# 09-Connectors.net
KiCad netlist of a schematic drawn in Altium Designer
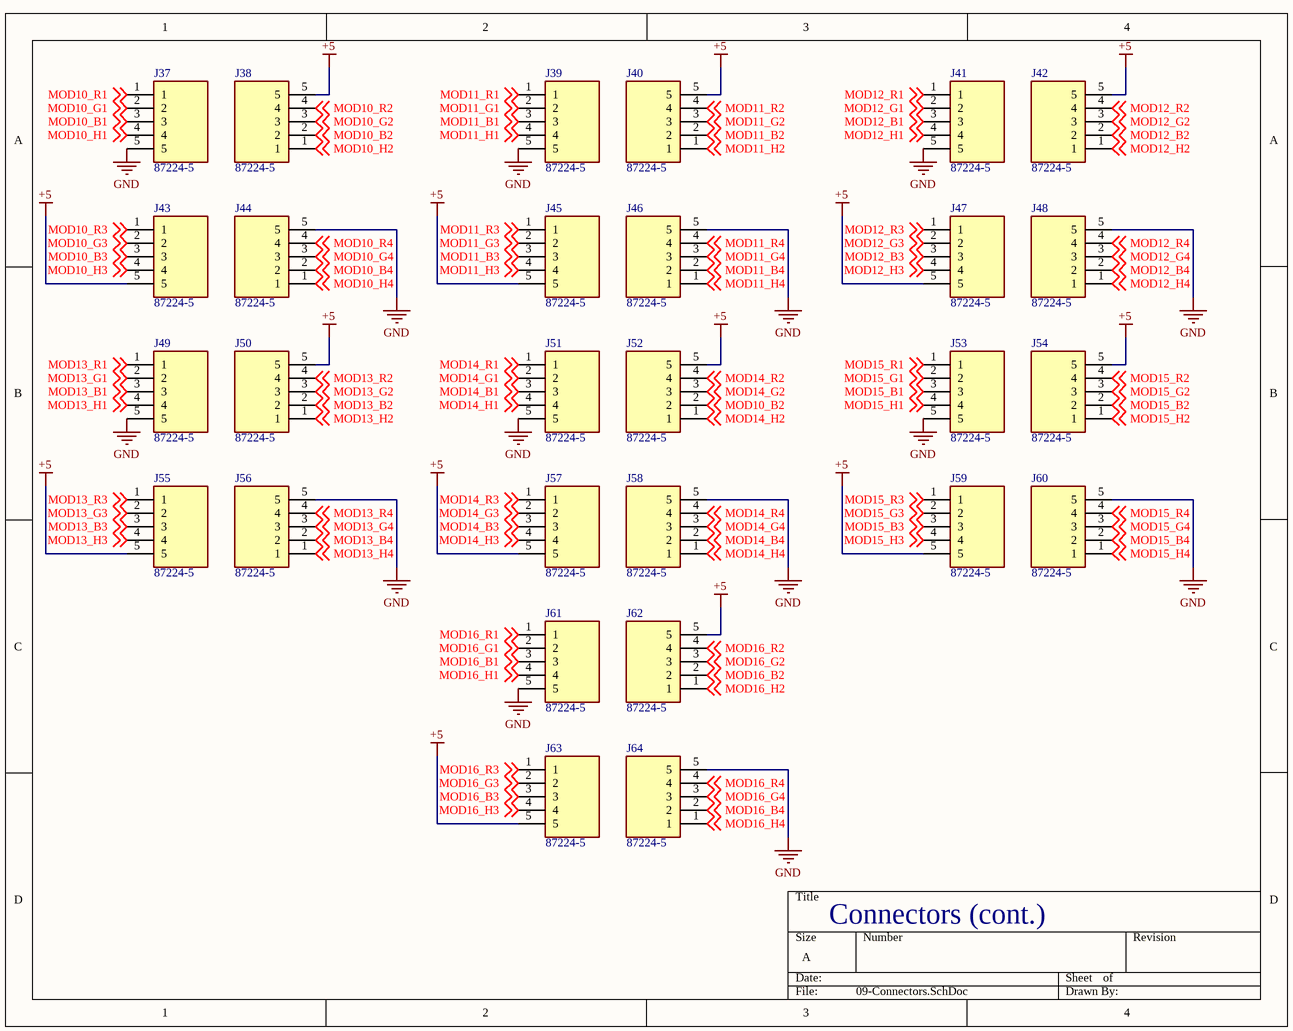
[diagram p0: 09-Connectors.SchDoc]

(export (version "E")
  (design (tool "Eeschema 10.0.6"))
  (components
    (comp (ref "J37")
      (value "87224-5")
      (footprint "TE_87224-5")
      (description "Conn Unshrouded Header HDR 5 POS 2.54mm Solder ST Thru-Hole")
      (fields (field (name "MF") "TE Connectivity"))
      (libsource (lib "chess_module") (part "87224-5"))
    )
    (comp (ref "J38")
      (value "87224-5")
      (footprint "TE_87224-5")
      (description "Conn Unshrouded Header HDR 5 POS 2.54mm Solder ST Thru-Hole")
      (fields (field (name "MF") "TE Connectivity"))
      (libsource (lib "") (part "87224-5_1"))
    )
    (comp (ref "J39")
      (value "87224-5")
      (footprint "TE_87224-5")
      (description "Conn Unshrouded Header HDR 5 POS 2.54mm Solder ST Thru-Hole")
      (fields (field (name "MF") "TE Connectivity"))
      (libsource (lib "chess_module") (part "87224-5"))
    )
    (comp (ref "J40")
      (value "87224-5")
      (footprint "TE_87224-5")
      (description "Conn Unshrouded Header HDR 5 POS 2.54mm Solder ST Thru-Hole")
      (fields (field (name "MF") "TE Connectivity"))
      (libsource (lib "") (part "87224-5_1"))
    )
    (comp (ref "J41")
      (value "87224-5")
      (footprint "TE_87224-5")
      (description "Conn Unshrouded Header HDR 5 POS 2.54mm Solder ST Thru-Hole")
      (fields (field (name "MF") "TE Connectivity"))
      (libsource (lib "chess_module") (part "87224-5"))
    )
    (comp (ref "J42")
      (value "87224-5")
      (footprint "TE_87224-5")
      (description "Conn Unshrouded Header HDR 5 POS 2.54mm Solder ST Thru-Hole")
      (fields (field (name "MF") "TE Connectivity"))
      (libsource (lib "") (part "87224-5_1"))
    )
    (comp (ref "J43")
      (value "87224-5")
      (footprint "TE_87224-5")
      (description "Conn Unshrouded Header HDR 5 POS 2.54mm Solder ST Thru-Hole")
      (fields (field (name "MF") "TE Connectivity"))
      (libsource (lib "chess_module") (part "87224-5"))
    )
    (comp (ref "J44")
      (value "87224-5")
      (footprint "TE_87224-5")
      (description "Conn Unshrouded Header HDR 5 POS 2.54mm Solder ST Thru-Hole")
      (fields (field (name "MF") "TE Connectivity"))
      (libsource (lib "") (part "87224-5_1"))
    )
    (comp (ref "J45")
      (value "87224-5")
      (footprint "TE_87224-5")
      (description "Conn Unshrouded Header HDR 5 POS 2.54mm Solder ST Thru-Hole")
      (fields (field (name "MF") "TE Connectivity"))
      (libsource (lib "chess_module") (part "87224-5"))
    )
    (comp (ref "J46")
      (value "87224-5")
      (footprint "TE_87224-5")
      (description "Conn Unshrouded Header HDR 5 POS 2.54mm Solder ST Thru-Hole")
      (fields (field (name "MF") "TE Connectivity"))
      (libsource (lib "") (part "87224-5_1"))
    )
    (comp (ref "J47")
      (value "87224-5")
      (footprint "TE_87224-5")
      (description "Conn Unshrouded Header HDR 5 POS 2.54mm Solder ST Thru-Hole")
      (fields (field (name "MF") "TE Connectivity"))
      (libsource (lib "chess_module") (part "87224-5"))
    )
    (comp (ref "J48")
      (value "87224-5")
      (footprint "TE_87224-5")
      (description "Conn Unshrouded Header HDR 5 POS 2.54mm Solder ST Thru-Hole")
      (fields (field (name "MF") "TE Connectivity"))
      (libsource (lib "") (part "87224-5_1"))
    )
    (comp (ref "J49")
      (value "87224-5")
      (footprint "TE_87224-5")
      (description "Conn Unshrouded Header HDR 5 POS 2.54mm Solder ST Thru-Hole")
      (fields (field (name "MF") "TE Connectivity"))
      (libsource (lib "chess_module") (part "87224-5"))
    )
    (comp (ref "J50")
      (value "87224-5")
      (footprint "TE_87224-5")
      (description "Conn Unshrouded Header HDR 5 POS 2.54mm Solder ST Thru-Hole")
      (fields (field (name "MF") "TE Connectivity"))
      (libsource (lib "") (part "87224-5_1"))
    )
    (comp (ref "J51")
      (value "87224-5")
      (footprint "TE_87224-5")
      (description "Conn Unshrouded Header HDR 5 POS 2.54mm Solder ST Thru-Hole")
      (fields (field (name "MF") "TE Connectivity"))
      (libsource (lib "chess_module") (part "87224-5"))
    )
    (comp (ref "J52")
      (value "87224-5")
      (footprint "TE_87224-5")
      (description "Conn Unshrouded Header HDR 5 POS 2.54mm Solder ST Thru-Hole")
      (fields (field (name "MF") "TE Connectivity"))
      (libsource (lib "") (part "87224-5_1"))
    )
    (comp (ref "J53")
      (value "87224-5")
      (footprint "TE_87224-5")
      (description "Conn Unshrouded Header HDR 5 POS 2.54mm Solder ST Thru-Hole")
      (fields (field (name "MF") "TE Connectivity"))
      (libsource (lib "chess_module") (part "87224-5"))
    )
    (comp (ref "J54")
      (value "87224-5")
      (footprint "TE_87224-5")
      (description "Conn Unshrouded Header HDR 5 POS 2.54mm Solder ST Thru-Hole")
      (fields (field (name "MF") "TE Connectivity"))
      (libsource (lib "") (part "87224-5_1"))
    )
    (comp (ref "J55")
      (value "87224-5")
      (footprint "TE_87224-5")
      (description "Conn Unshrouded Header HDR 5 POS 2.54mm Solder ST Thru-Hole")
      (fields (field (name "MF") "TE Connectivity"))
      (libsource (lib "chess_module") (part "87224-5"))
    )
    (comp (ref "J56")
      (value "87224-5")
      (footprint "TE_87224-5")
      (description "Conn Unshrouded Header HDR 5 POS 2.54mm Solder ST Thru-Hole")
      (fields (field (name "MF") "TE Connectivity"))
      (libsource (lib "") (part "87224-5_1"))
    )
    (comp (ref "J57")
      (value "87224-5")
      (footprint "TE_87224-5")
      (description "Conn Unshrouded Header HDR 5 POS 2.54mm Solder ST Thru-Hole")
      (fields (field (name "MF") "TE Connectivity"))
      (libsource (lib "chess_module") (part "87224-5"))
    )
    (comp (ref "J58")
      (value "87224-5")
      (footprint "TE_87224-5")
      (description "Conn Unshrouded Header HDR 5 POS 2.54mm Solder ST Thru-Hole")
      (fields (field (name "MF") "TE Connectivity"))
      (libsource (lib "") (part "87224-5_1"))
    )
    (comp (ref "J59")
      (value "87224-5")
      (footprint "TE_87224-5")
      (description "Conn Unshrouded Header HDR 5 POS 2.54mm Solder ST Thru-Hole")
      (fields (field (name "MF") "TE Connectivity"))
      (libsource (lib "chess_module") (part "87224-5"))
    )
    (comp (ref "J60")
      (value "87224-5")
      (footprint "TE_87224-5")
      (description "Conn Unshrouded Header HDR 5 POS 2.54mm Solder ST Thru-Hole")
      (fields (field (name "MF") "TE Connectivity"))
      (libsource (lib "") (part "87224-5_1"))
    )
    (comp (ref "J61")
      (value "87224-5")
      (footprint "TE_87224-5")
      (description "Conn Unshrouded Header HDR 5 POS 2.54mm Solder ST Thru-Hole")
      (fields (field (name "MF") "TE Connectivity"))
      (libsource (lib "chess_module") (part "87224-5"))
    )
    (comp (ref "J62")
      (value "87224-5")
      (footprint "TE_87224-5")
      (description "Conn Unshrouded Header HDR 5 POS 2.54mm Solder ST Thru-Hole")
      (fields (field (name "MF") "TE Connectivity"))
      (libsource (lib "") (part "87224-5_1"))
    )
    (comp (ref "J63")
      (value "87224-5")
      (footprint "TE_87224-5")
      (description "Conn Unshrouded Header HDR 5 POS 2.54mm Solder ST Thru-Hole")
      (fields (field (name "MF") "TE Connectivity"))
      (libsource (lib "chess_module") (part "87224-5"))
    )
    (comp (ref "J64")
      (value "87224-5")
      (footprint "TE_87224-5")
      (description "Conn Unshrouded Header HDR 5 POS 2.54mm Solder ST Thru-Hole")
      (fields (field (name "MF") "TE Connectivity"))
      (libsource (lib "") (part "87224-5_1"))
    )
  )
  (nets
    (net (code "1") (name "+5") (class "Default")
      (node (ref "J38") (pin "5") (pinfunction "5_5") (pintype "passive"))
      (node (ref "J40") (pin "5") (pinfunction "5_5") (pintype "passive"))
      (node (ref "J42") (pin "5") (pinfunction "5_5") (pintype "passive"))
      (node (ref "J43") (pin "5") (pinfunction "5_5") (pintype "passive"))
      (node (ref "J45") (pin "5") (pinfunction "5_5") (pintype "passive"))
      (node (ref "J47") (pin "5") (pinfunction "5_5") (pintype "passive"))
      (node (ref "J50") (pin "5") (pinfunction "5_5") (pintype "passive"))
      (node (ref "J52") (pin "5") (pinfunction "5_5") (pintype "passive"))
      (node (ref "J54") (pin "5") (pinfunction "5_5") (pintype "passive"))
      (node (ref "J55") (pin "5") (pinfunction "5_5") (pintype "passive"))
      (node (ref "J57") (pin "5") (pinfunction "5_5") (pintype "passive"))
      (node (ref "J59") (pin "5") (pinfunction "5_5") (pintype "passive"))
      (node (ref "J62") (pin "5") (pinfunction "5_5") (pintype "passive"))
      (node (ref "J63") (pin "5") (pinfunction "5_5") (pintype "passive"))
    )
    (net (code "2") (name "GND") (class "Default")
      (node (ref "J37") (pin "5") (pinfunction "5_5") (pintype "passive"))
      (node (ref "J39") (pin "5") (pinfunction "5_5") (pintype "passive"))
      (node (ref "J41") (pin "5") (pinfunction "5_5") (pintype "passive"))
      (node (ref "J44") (pin "5") (pinfunction "5_5") (pintype "passive"))
      (node (ref "J46") (pin "5") (pinfunction "5_5") (pintype "passive"))
      (node (ref "J48") (pin "5") (pinfunction "5_5") (pintype "passive"))
      (node (ref "J49") (pin "5") (pinfunction "5_5") (pintype "passive"))
      (node (ref "J51") (pin "5") (pinfunction "5_5") (pintype "passive"))
      (node (ref "J53") (pin "5") (pinfunction "5_5") (pintype "passive"))
      (node (ref "J56") (pin "5") (pinfunction "5_5") (pintype "passive"))
      (node (ref "J58") (pin "5") (pinfunction "5_5") (pintype "passive"))
      (node (ref "J60") (pin "5") (pinfunction "5_5") (pintype "passive"))
      (node (ref "J61") (pin "5") (pinfunction "5_5") (pintype "passive"))
      (node (ref "J64") (pin "5") (pinfunction "5_5") (pintype "passive"))
    )
    (net (code "3") (name "MOD10_B1") (class "Default")
      (node (ref "J37") (pin "3") (pinfunction "3_3") (pintype "passive"))
    )
    (net (code "4") (name "MOD10_B2") (class "Default")
      (node (ref "J38") (pin "2") (pinfunction "2_2") (pintype "passive"))
      (node (ref "J52") (pin "2") (pinfunction "2_2") (pintype "passive"))
    )
    (net (code "5") (name "MOD10_B3") (class "Default")
      (node (ref "J43") (pin "3") (pinfunction "3_3") (pintype "passive"))
    )
    (net (code "6") (name "MOD10_B4") (class "Default")
      (node (ref "J44") (pin "2") (pinfunction "2_2") (pintype "passive"))
    )
    (net (code "7") (name "MOD10_G1") (class "Default")
      (node (ref "J37") (pin "2") (pinfunction "2_2") (pintype "passive"))
    )
    (net (code "8") (name "MOD10_G2") (class "Default")
      (node (ref "J38") (pin "3") (pinfunction "3_3") (pintype "passive"))
    )
    (net (code "9") (name "MOD10_G3") (class "Default")
      (node (ref "J43") (pin "2") (pinfunction "2_2") (pintype "passive"))
    )
    (net (code "10") (name "MOD10_G4") (class "Default")
      (node (ref "J44") (pin "3") (pinfunction "3_3") (pintype "passive"))
    )
    (net (code "11") (name "MOD10_H1") (class "Default")
      (node (ref "J37") (pin "4") (pinfunction "4_4") (pintype "passive"))
    )
    (net (code "12") (name "MOD10_H2") (class "Default")
      (node (ref "J38") (pin "1") (pinfunction "1_1") (pintype "passive"))
    )
    (net (code "13") (name "MOD10_H3") (class "Default")
      (node (ref "J43") (pin "4") (pinfunction "4_4") (pintype "passive"))
    )
    (net (code "14") (name "MOD10_H4") (class "Default")
      (node (ref "J44") (pin "1") (pinfunction "1_1") (pintype "passive"))
    )
    (net (code "15") (name "MOD10_R1") (class "Default")
      (node (ref "J37") (pin "1") (pinfunction "1_1") (pintype "passive"))
    )
    (net (code "16") (name "MOD10_R2") (class "Default")
      (node (ref "J38") (pin "4") (pinfunction "4_4") (pintype "passive"))
    )
    (net (code "17") (name "MOD10_R3") (class "Default")
      (node (ref "J43") (pin "1") (pinfunction "1_1") (pintype "passive"))
    )
    (net (code "18") (name "MOD10_R4") (class "Default")
      (node (ref "J44") (pin "4") (pinfunction "4_4") (pintype "passive"))
    )
    (net (code "19") (name "MOD11_B1") (class "Default")
      (node (ref "J39") (pin "3") (pinfunction "3_3") (pintype "passive"))
    )
    (net (code "20") (name "MOD11_B2") (class "Default")
      (node (ref "J40") (pin "2") (pinfunction "2_2") (pintype "passive"))
    )
    (net (code "21") (name "MOD11_B3") (class "Default")
      (node (ref "J45") (pin "3") (pinfunction "3_3") (pintype "passive"))
    )
    (net (code "22") (name "MOD11_B4") (class "Default")
      (node (ref "J46") (pin "2") (pinfunction "2_2") (pintype "passive"))
    )
    (net (code "23") (name "MOD11_G1") (class "Default")
      (node (ref "J39") (pin "2") (pinfunction "2_2") (pintype "passive"))
    )
    (net (code "24") (name "MOD11_G2") (class "Default")
      (node (ref "J40") (pin "3") (pinfunction "3_3") (pintype "passive"))
    )
    (net (code "25") (name "MOD11_G3") (class "Default")
      (node (ref "J45") (pin "2") (pinfunction "2_2") (pintype "passive"))
    )
    (net (code "26") (name "MOD11_G4") (class "Default")
      (node (ref "J46") (pin "3") (pinfunction "3_3") (pintype "passive"))
    )
    (net (code "27") (name "MOD11_H1") (class "Default")
      (node (ref "J39") (pin "4") (pinfunction "4_4") (pintype "passive"))
    )
    (net (code "28") (name "MOD11_H2") (class "Default")
      (node (ref "J40") (pin "1") (pinfunction "1_1") (pintype "passive"))
    )
    (net (code "29") (name "MOD11_H3") (class "Default")
      (node (ref "J45") (pin "4") (pinfunction "4_4") (pintype "passive"))
    )
    (net (code "30") (name "MOD11_H4") (class "Default")
      (node (ref "J46") (pin "1") (pinfunction "1_1") (pintype "passive"))
    )
    (net (code "31") (name "MOD11_R1") (class "Default")
      (node (ref "J39") (pin "1") (pinfunction "1_1") (pintype "passive"))
    )
    (net (code "32") (name "MOD11_R2") (class "Default")
      (node (ref "J40") (pin "4") (pinfunction "4_4") (pintype "passive"))
    )
    (net (code "33") (name "MOD11_R3") (class "Default")
      (node (ref "J45") (pin "1") (pinfunction "1_1") (pintype "passive"))
    )
    (net (code "34") (name "MOD11_R4") (class "Default")
      (node (ref "J46") (pin "4") (pinfunction "4_4") (pintype "passive"))
    )
    (net (code "35") (name "MOD12_B1") (class "Default")
      (node (ref "J41") (pin "3") (pinfunction "3_3") (pintype "passive"))
    )
    (net (code "36") (name "MOD12_B2") (class "Default")
      (node (ref "J42") (pin "2") (pinfunction "2_2") (pintype "passive"))
    )
    (net (code "37") (name "MOD12_B3") (class "Default")
      (node (ref "J47") (pin "3") (pinfunction "3_3") (pintype "passive"))
    )
    (net (code "38") (name "MOD12_B4") (class "Default")
      (node (ref "J48") (pin "2") (pinfunction "2_2") (pintype "passive"))
    )
    (net (code "39") (name "MOD12_G1") (class "Default")
      (node (ref "J41") (pin "2") (pinfunction "2_2") (pintype "passive"))
    )
    (net (code "40") (name "MOD12_G2") (class "Default")
      (node (ref "J42") (pin "3") (pinfunction "3_3") (pintype "passive"))
    )
    (net (code "41") (name "MOD12_G3") (class "Default")
      (node (ref "J47") (pin "2") (pinfunction "2_2") (pintype "passive"))
    )
    (net (code "42") (name "MOD12_G4") (class "Default")
      (node (ref "J48") (pin "3") (pinfunction "3_3") (pintype "passive"))
    )
    (net (code "43") (name "MOD12_H1") (class "Default")
      (node (ref "J41") (pin "4") (pinfunction "4_4") (pintype "passive"))
    )
    (net (code "44") (name "MOD12_H2") (class "Default")
      (node (ref "J42") (pin "1") (pinfunction "1_1") (pintype "passive"))
    )
    (net (code "45") (name "MOD12_H3") (class "Default")
      (node (ref "J47") (pin "4") (pinfunction "4_4") (pintype "passive"))
    )
    (net (code "46") (name "MOD12_H4") (class "Default")
      (node (ref "J48") (pin "1") (pinfunction "1_1") (pintype "passive"))
    )
    (net (code "47") (name "MOD12_R1") (class "Default")
      (node (ref "J41") (pin "1") (pinfunction "1_1") (pintype "passive"))
    )
    (net (code "48") (name "MOD12_R2") (class "Default")
      (node (ref "J42") (pin "4") (pinfunction "4_4") (pintype "passive"))
    )
    (net (code "49") (name "MOD12_R3") (class "Default")
      (node (ref "J47") (pin "1") (pinfunction "1_1") (pintype "passive"))
    )
    (net (code "50") (name "MOD12_R4") (class "Default")
      (node (ref "J48") (pin "4") (pinfunction "4_4") (pintype "passive"))
    )
    (net (code "51") (name "MOD13_B1") (class "Default")
      (node (ref "J49") (pin "3") (pinfunction "3_3") (pintype "passive"))
    )
    (net (code "52") (name "MOD13_B2") (class "Default")
      (node (ref "J50") (pin "2") (pinfunction "2_2") (pintype "passive"))
    )
    (net (code "53") (name "MOD13_B3") (class "Default")
      (node (ref "J55") (pin "3") (pinfunction "3_3") (pintype "passive"))
    )
    (net (code "54") (name "MOD13_B4") (class "Default")
      (node (ref "J56") (pin "2") (pinfunction "2_2") (pintype "passive"))
    )
    (net (code "55") (name "MOD13_G1") (class "Default")
      (node (ref "J49") (pin "2") (pinfunction "2_2") (pintype "passive"))
    )
    (net (code "56") (name "MOD13_G2") (class "Default")
      (node (ref "J50") (pin "3") (pinfunction "3_3") (pintype "passive"))
    )
    (net (code "57") (name "MOD13_G3") (class "Default")
      (node (ref "J55") (pin "2") (pinfunction "2_2") (pintype "passive"))
    )
    (net (code "58") (name "MOD13_G4") (class "Default")
      (node (ref "J56") (pin "3") (pinfunction "3_3") (pintype "passive"))
    )
    (net (code "59") (name "MOD13_H1") (class "Default")
      (node (ref "J49") (pin "4") (pinfunction "4_4") (pintype "passive"))
    )
    (net (code "60") (name "MOD13_H2") (class "Default")
      (node (ref "J50") (pin "1") (pinfunction "1_1") (pintype "passive"))
    )
    (net (code "61") (name "MOD13_H3") (class "Default")
      (node (ref "J55") (pin "4") (pinfunction "4_4") (pintype "passive"))
    )
    (net (code "62") (name "MOD13_H4") (class "Default")
      (node (ref "J56") (pin "1") (pinfunction "1_1") (pintype "passive"))
    )
    (net (code "63") (name "MOD13_R1") (class "Default")
      (node (ref "J49") (pin "1") (pinfunction "1_1") (pintype "passive"))
    )
    (net (code "64") (name "MOD13_R2") (class "Default")
      (node (ref "J50") (pin "4") (pinfunction "4_4") (pintype "passive"))
    )
    (net (code "65") (name "MOD13_R3") (class "Default")
      (node (ref "J55") (pin "1") (pinfunction "1_1") (pintype "passive"))
    )
    (net (code "66") (name "MOD13_R4") (class "Default")
      (node (ref "J56") (pin "4") (pinfunction "4_4") (pintype "passive"))
    )
    (net (code "67") (name "MOD14_B1") (class "Default")
      (node (ref "J51") (pin "3") (pinfunction "3_3") (pintype "passive"))
    )
    (net (code "68") (name "MOD14_B3") (class "Default")
      (node (ref "J57") (pin "3") (pinfunction "3_3") (pintype "passive"))
    )
    (net (code "69") (name "MOD14_B4") (class "Default")
      (node (ref "J58") (pin "2") (pinfunction "2_2") (pintype "passive"))
    )
    (net (code "70") (name "MOD14_G1") (class "Default")
      (node (ref "J51") (pin "2") (pinfunction "2_2") (pintype "passive"))
    )
    (net (code "71") (name "MOD14_G2") (class "Default")
      (node (ref "J52") (pin "3") (pinfunction "3_3") (pintype "passive"))
    )
    (net (code "72") (name "MOD14_G3") (class "Default")
      (node (ref "J57") (pin "2") (pinfunction "2_2") (pintype "passive"))
    )
    (net (code "73") (name "MOD14_G4") (class "Default")
      (node (ref "J58") (pin "3") (pinfunction "3_3") (pintype "passive"))
    )
    (net (code "74") (name "MOD14_H1") (class "Default")
      (node (ref "J51") (pin "4") (pinfunction "4_4") (pintype "passive"))
    )
    (net (code "75") (name "MOD14_H2") (class "Default")
      (node (ref "J52") (pin "1") (pinfunction "1_1") (pintype "passive"))
    )
    (net (code "76") (name "MOD14_H3") (class "Default")
      (node (ref "J57") (pin "4") (pinfunction "4_4") (pintype "passive"))
    )
    (net (code "77") (name "MOD14_H4") (class "Default")
      (node (ref "J58") (pin "1") (pinfunction "1_1") (pintype "passive"))
    )
    (net (code "78") (name "MOD14_R1") (class "Default")
      (node (ref "J51") (pin "1") (pinfunction "1_1") (pintype "passive"))
    )
    (net (code "79") (name "MOD14_R2") (class "Default")
      (node (ref "J52") (pin "4") (pinfunction "4_4") (pintype "passive"))
    )
    (net (code "80") (name "MOD14_R3") (class "Default")
      (node (ref "J57") (pin "1") (pinfunction "1_1") (pintype "passive"))
    )
    (net (code "81") (name "MOD14_R4") (class "Default")
      (node (ref "J58") (pin "4") (pinfunction "4_4") (pintype "passive"))
    )
    (net (code "82") (name "MOD15_B1") (class "Default")
      (node (ref "J53") (pin "3") (pinfunction "3_3") (pintype "passive"))
    )
    (net (code "83") (name "MOD15_B2") (class "Default")
      (node (ref "J54") (pin "2") (pinfunction "2_2") (pintype "passive"))
    )
    (net (code "84") (name "MOD15_B3") (class "Default")
      (node (ref "J59") (pin "3") (pinfunction "3_3") (pintype "passive"))
    )
    (net (code "85") (name "MOD15_B4") (class "Default")
      (node (ref "J60") (pin "2") (pinfunction "2_2") (pintype "passive"))
    )
    (net (code "86") (name "MOD15_G1") (class "Default")
      (node (ref "J53") (pin "2") (pinfunction "2_2") (pintype "passive"))
    )
    (net (code "87") (name "MOD15_G2") (class "Default")
      (node (ref "J54") (pin "3") (pinfunction "3_3") (pintype "passive"))
    )
    (net (code "88") (name "MOD15_G3") (class "Default")
      (node (ref "J59") (pin "2") (pinfunction "2_2") (pintype "passive"))
    )
    (net (code "89") (name "MOD15_G4") (class "Default")
      (node (ref "J60") (pin "3") (pinfunction "3_3") (pintype "passive"))
    )
    (net (code "90") (name "MOD15_H1") (class "Default")
      (node (ref "J53") (pin "4") (pinfunction "4_4") (pintype "passive"))
    )
    (net (code "91") (name "MOD15_H2") (class "Default")
      (node (ref "J54") (pin "1") (pinfunction "1_1") (pintype "passive"))
    )
    (net (code "92") (name "MOD15_H3") (class "Default")
      (node (ref "J59") (pin "4") (pinfunction "4_4") (pintype "passive"))
    )
    (net (code "93") (name "MOD15_H4") (class "Default")
      (node (ref "J60") (pin "1") (pinfunction "1_1") (pintype "passive"))
    )
    (net (code "94") (name "MOD15_R1") (class "Default")
      (node (ref "J53") (pin "1") (pinfunction "1_1") (pintype "passive"))
    )
    (net (code "95") (name "MOD15_R2") (class "Default")
      (node (ref "J54") (pin "4") (pinfunction "4_4") (pintype "passive"))
    )
    (net (code "96") (name "MOD15_R3") (class "Default")
      (node (ref "J59") (pin "1") (pinfunction "1_1") (pintype "passive"))
    )
    (net (code "97") (name "MOD15_R4") (class "Default")
      (node (ref "J60") (pin "4") (pinfunction "4_4") (pintype "passive"))
    )
    (net (code "98") (name "MOD16_B1") (class "Default")
      (node (ref "J61") (pin "3") (pinfunction "3_3") (pintype "passive"))
    )
    (net (code "99") (name "MOD16_B2") (class "Default")
      (node (ref "J62") (pin "2") (pinfunction "2_2") (pintype "passive"))
    )
    (net (code "100") (name "MOD16_B3") (class "Default")
      (node (ref "J63") (pin "3") (pinfunction "3_3") (pintype "passive"))
    )
    (net (code "101") (name "MOD16_B4") (class "Default")
      (node (ref "J64") (pin "2") (pinfunction "2_2") (pintype "passive"))
    )
    (net (code "102") (name "MOD16_G1") (class "Default")
      (node (ref "J61") (pin "2") (pinfunction "2_2") (pintype "passive"))
    )
    (net (code "103") (name "MOD16_G2") (class "Default")
      (node (ref "J62") (pin "3") (pinfunction "3_3") (pintype "passive"))
    )
    (net (code "104") (name "MOD16_G3") (class "Default")
      (node (ref "J63") (pin "2") (pinfunction "2_2") (pintype "passive"))
    )
    (net (code "105") (name "MOD16_G4") (class "Default")
      (node (ref "J64") (pin "3") (pinfunction "3_3") (pintype "passive"))
    )
    (net (code "106") (name "MOD16_H1") (class "Default")
      (node (ref "J61") (pin "4") (pinfunction "4_4") (pintype "passive"))
    )
    (net (code "107") (name "MOD16_H2") (class "Default")
      (node (ref "J62") (pin "1") (pinfunction "1_1") (pintype "passive"))
    )
    (net (code "108") (name "MOD16_H3") (class "Default")
      (node (ref "J63") (pin "4") (pinfunction "4_4") (pintype "passive"))
    )
    (net (code "109") (name "MOD16_H4") (class "Default")
      (node (ref "J64") (pin "1") (pinfunction "1_1") (pintype "passive"))
    )
    (net (code "110") (name "MOD16_R1") (class "Default")
      (node (ref "J61") (pin "1") (pinfunction "1_1") (pintype "passive"))
    )
    (net (code "111") (name "MOD16_R2") (class "Default")
      (node (ref "J62") (pin "4") (pinfunction "4_4") (pintype "passive"))
    )
    (net (code "112") (name "MOD16_R3") (class "Default")
      (node (ref "J63") (pin "1") (pinfunction "1_1") (pintype "passive"))
    )
    (net (code "113") (name "MOD16_R4") (class "Default")
      (node (ref "J64") (pin "4") (pinfunction "4_4") (pintype "passive"))
    )
  )
)
